# 1U_LFO.net
KiCad netlist of a schematic drawn in EAGLE
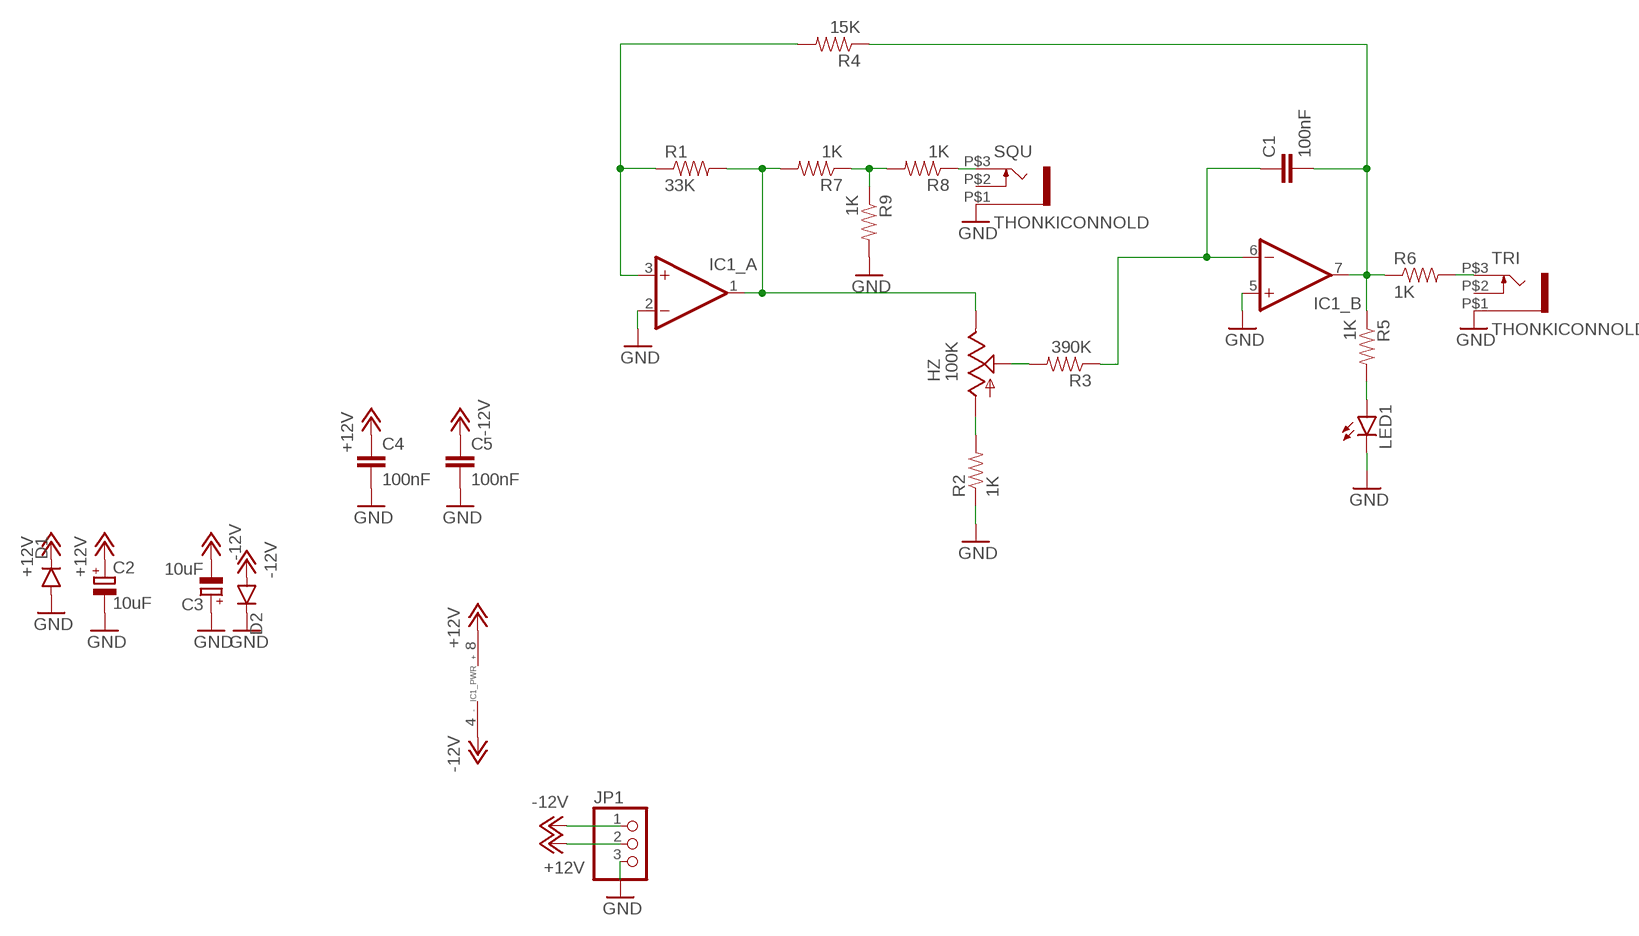
[diagram p0: schematic, sheet 1]

(export (version "E")
  (design (tool "Eeschema 10.0.6"))
  (components
    (comp (ref "C1")
      (value "100nF")
      (footprint "eagle-import:0603-CAP")
      (libsource (lib "eagle-import") (part "CAP0603-CAP"))
    )
    (comp (ref "C2")
      (value "10uF")
      (footprint "eagle-import:CASE_B")
      (libsource (lib "eagle-import") (part "CAPACITOR_POL-CASE_B"))
    )
    (comp (ref "C3")
      (value "10uF")
      (footprint "eagle-import:CASE_B")
      (libsource (lib "eagle-import") (part "CAPACITOR_POL-CASE_B"))
    )
    (comp (ref "C4")
      (value "100nF")
      (footprint "eagle-import:0603-CAP")
      (libsource (lib "eagle-import") (part "CAP0603-CAP"))
    )
    (comp (ref "C5")
      (value "100nF")
      (footprint "eagle-import:0603-CAP")
      (libsource (lib "eagle-import") (part "CAP0603-CAP"))
    )
    (comp (ref "D1")
      (value "DIODESOD123")
      (footprint "eagle-import:SOD-123")
      (libsource (lib "eagle-import") (part "DIODESOD123"))
    )
    (comp (ref "D2")
      (value "DIODESOD123")
      (footprint "eagle-import:SOD-123")
      (libsource (lib "eagle-import") (part "DIODESOD123"))
    )
    (comp (ref "HZ")
      (value "100K")
      (footprint "eagle-import:9MM_SNAP-IN_POT")
      (libsource (lib "eagle-import") (part "9MM_SNAP-IN_POT_"))
    )
    (comp (ref "IC1")
      (value "DUALSMD")
      (footprint "eagle-import:SO08")
      (libsource (lib "eagle-import") (part "DUALSMD"))
    )
    (comp (ref "JP1")
      (value "EUROPWR_TILE-TILE")
      (footprint "eagle-import:1X03_EUROPWR_TILE")
      (libsource (lib "eagle-import") (part "EUROPWR_TILE-TILE"))
    )
    (comp (ref "LED1")
      (value "LED3MM")
      (footprint "eagle-import:LED3MM")
      (libsource (lib "eagle-import") (part "LED3MM"))
    )
    (comp (ref "R1")
      (value "33K")
      (footprint "eagle-import:0603-RES")
      (libsource (lib "eagle-import") (part "RESISTOR0603-RES"))
    )
    (comp (ref "R2")
      (value "1K")
      (footprint "eagle-import:0603-RES")
      (libsource (lib "eagle-import") (part "RESISTOR0603-RES"))
    )
    (comp (ref "R3")
      (value "390K")
      (footprint "eagle-import:0603-RES")
      (libsource (lib "eagle-import") (part "RESISTOR0603-RES"))
    )
    (comp (ref "R4")
      (value "15K")
      (footprint "eagle-import:0603-RES")
      (libsource (lib "eagle-import") (part "RESISTOR0603-RES"))
    )
    (comp (ref "R5")
      (value "1K")
      (footprint "eagle-import:0603-RES")
      (libsource (lib "eagle-import") (part "RESISTOR0603-RES"))
    )
    (comp (ref "R6")
      (value "1K")
      (footprint "eagle-import:0603-RES")
      (libsource (lib "eagle-import") (part "RESISTOR0603-RES"))
    )
    (comp (ref "R7")
      (value "1K")
      (footprint "eagle-import:0603-RES")
      (libsource (lib "eagle-import") (part "RESISTOR0603-RES"))
    )
    (comp (ref "R8")
      (value "1K")
      (footprint "eagle-import:0603-RES")
      (libsource (lib "eagle-import") (part "RESISTOR0603-RES"))
    )
    (comp (ref "R9")
      (value "1K")
      (footprint "eagle-import:0603-RES")
      (libsource (lib "eagle-import") (part "RESISTOR0603-RES"))
    )
    (comp (ref "SQU")
      (value "THONKICONNOLD")
      (footprint "eagle-import:THONKICONN")
      (libsource (lib "eagle-import") (part "THONKICONNOLD"))
    )
    (comp (ref "TRI")
      (value "THONKICONNOLD")
      (footprint "eagle-import:THONKICONN")
      (libsource (lib "eagle-import") (part "THONKICONNOLD"))
    )
  )
  (nets
    (net (code "1") (name "+12V") (class "Default")
      (node (ref "C2") (pin "+") (pinfunction "+_+") (pintype "passive"))
      (node (ref "C4") (pin "1") (pinfunction "1_1") (pintype "passive"))
      (node (ref "D1") (pin "C") (pinfunction "C_C") (pintype "passive"))
      (node (ref "IC1") (pin "8") (pinfunction "V+_8") (pintype "power_in"))
      (node (ref "JP1") (pin "2") (pinfunction "2_2") (pintype "passive"))
    )
    (net (code "2") (name "-12V") (class "Default")
      (node (ref "C3") (pin "-") (pinfunction "-_-") (pintype "passive"))
      (node (ref "C5") (pin "1") (pinfunction "1_1") (pintype "passive"))
      (node (ref "D2") (pin "A") (pinfunction "A_A") (pintype "passive"))
      (node (ref "IC1") (pin "4") (pinfunction "V-_4") (pintype "power_in"))
      (node (ref "JP1") (pin "1") (pinfunction "1_1") (pintype "passive"))
    )
    (net (code "3") (name "GND") (class "Default")
      (node (ref "C2") (pin "-") (pinfunction "-_-") (pintype "passive"))
      (node (ref "C3") (pin "+") (pinfunction "+_+") (pintype "passive"))
      (node (ref "C4") (pin "2") (pinfunction "2_2") (pintype "passive"))
      (node (ref "C5") (pin "2") (pinfunction "2_2") (pintype "passive"))
      (node (ref "D1") (pin "A") (pinfunction "A_A") (pintype "passive"))
      (node (ref "D2") (pin "C") (pinfunction "C_C") (pintype "passive"))
      (node (ref "IC1") (pin "2") (pinfunction "-IN_2") (pintype "input"))
      (node (ref "IC1") (pin "5") (pinfunction "+IN_5") (pintype "input"))
      (node (ref "JP1") (pin "3") (pinfunction "3_3") (pintype "passive"))
      (node (ref "LED1") (pin "K") (pinfunction "C_K") (pintype "passive"))
      (node (ref "R2") (pin "1") (pinfunction "1_1") (pintype "passive"))
      (node (ref "R9") (pin "2") (pinfunction "2_2") (pintype "passive"))
      (node (ref "SQU") (pin "P$1") (pinfunction "5_P$1") (pintype "passive"))
      (node (ref "TRI") (pin "P$1") (pinfunction "5_P$1") (pintype "passive"))
    )
    (net (code "4") (name "Net-(HZ-A)") (class "Default")
      (node (ref "HZ") (pin "1") (pinfunction "A_1") (pintype "passive"))
      (node (ref "R2") (pin "2") (pinfunction "2_2") (pintype "passive"))
    )
    (net (code "5") (name "Net-(HZ-E)") (class "Default")
      (node (ref "HZ") (pin "3") (pinfunction "E_3") (pintype "passive"))
      (node (ref "IC1") (pin "1") (pinfunction "OUT_1") (pintype "output"))
      (node (ref "R1") (pin "2") (pinfunction "2_2") (pintype "passive"))
      (node (ref "R7") (pin "2") (pinfunction "2_2") (pintype "passive"))
    )
    (net (code "6") (name "Net-(HZ-S)") (class "Default")
      (node (ref "HZ") (pin "2") (pinfunction "S_2") (pintype "passive"))
      (node (ref "R3") (pin "2") (pinfunction "2_2") (pintype "passive"))
    )
    (net (code "7") (name "Net-(IC1A-+IN)") (class "Default")
      (node (ref "IC1") (pin "3") (pinfunction "+IN_3") (pintype "input"))
      (node (ref "R1") (pin "1") (pinfunction "1_1") (pintype "passive"))
      (node (ref "R4") (pin "2") (pinfunction "2_2") (pintype "passive"))
    )
    (net (code "8") (name "Net-(IC1B--IN)") (class "Default")
      (node (ref "C1") (pin "1") (pinfunction "1_1") (pintype "passive"))
      (node (ref "IC1") (pin "6") (pinfunction "-IN_6") (pintype "input"))
      (node (ref "R3") (pin "1") (pinfunction "1_1") (pintype "passive"))
    )
    (net (code "9") (name "Net-(IC1B-OUT)") (class "Default")
      (node (ref "C1") (pin "2") (pinfunction "2_2") (pintype "passive"))
      (node (ref "IC1") (pin "7") (pinfunction "OUT_7") (pintype "output"))
      (node (ref "R4") (pin "1") (pinfunction "1_1") (pintype "passive"))
      (node (ref "R5") (pin "1") (pinfunction "1_1") (pintype "passive"))
      (node (ref "R6") (pin "1") (pinfunction "1_1") (pintype "passive"))
    )
    (net (code "10") (name "Net-(LED1-PadA)") (class "Default")
      (node (ref "LED1") (pin "A") (pinfunction "A_A") (pintype "passive"))
      (node (ref "R5") (pin "2") (pinfunction "2_2") (pintype "passive"))
    )
    (net (code "11") (name "Net-(R7-Pad1)") (class "Default")
      (node (ref "R7") (pin "1") (pinfunction "1_1") (pintype "passive"))
      (node (ref "R8") (pin "2") (pinfunction "2_2") (pintype "passive"))
      (node (ref "R9") (pin "1") (pinfunction "1_1") (pintype "passive"))
    )
    (net (code "12") (name "Net-(SQU-3)") (class "Default")
      (node (ref "R8") (pin "1") (pinfunction "1_1") (pintype "passive"))
      (node (ref "SQU") (pin "P$3") (pinfunction "3_P$3") (pintype "passive"))
    )
    (net (code "13") (name "Net-(TRI-3)") (class "Default")
      (node (ref "R6") (pin "2") (pinfunction "2_2") (pintype "passive"))
      (node (ref "TRI") (pin "P$3") (pinfunction "3_P$3") (pintype "passive"))
    )
    (net (code "14") (name "unconnected-(SQU-4-PadP$2)") (class "Default")
      (node (ref "SQU") (pin "P$2") (pinfunction "4_P$2") (pintype "passive"))
    )
    (net (code "15") (name "unconnected-(TRI-4-PadP$2)") (class "Default")
      (node (ref "TRI") (pin "P$2") (pinfunction "4_P$2") (pintype "passive"))
    )
  )
)
